# NTCSHTshield.net
KiCad netlist of a schematic drawn in EAGLE
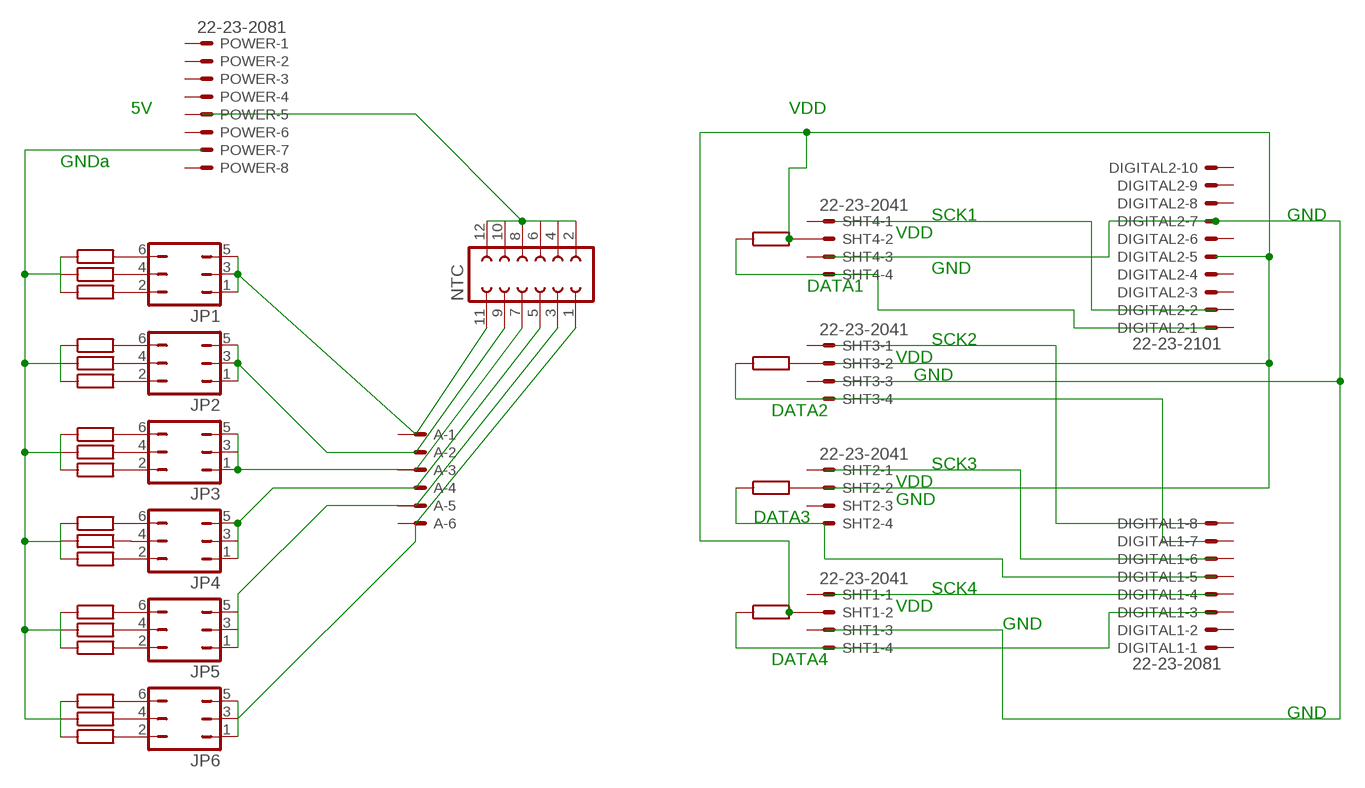
[diagram p0: schematic, sheet 1]

(export (version "E")
  (design (tool "Eeschema 10.0.6"))
  (components
    (comp (ref "A")
      (value "22-23-2061")
      (footprint "eagle-import:22-23-2061")
      (fields (field (name "MF") "MOLEX"))
      (libsource (lib "eagle-import") (part "22-23-2061"))
    )
    (comp (ref "DIGITAL1")
      (value "22-23-2081")
      (footprint "eagle-import:22-23-2081")
      (fields (field (name "MF") "MOLEX"))
      (libsource (lib "eagle-import") (part "22-23-2081"))
    )
    (comp (ref "DIGITAL2")
      (value "22-23-2101")
      (footprint "eagle-import:22-23-2101")
      (fields (field (name "MF") "MOLEX"))
      (libsource (lib "eagle-import") (part "22-23-2101"))
    )
    (comp (ref "JP1")
      (value "JP3Q")
      (footprint "eagle-import:JP3Q")
      (libsource (lib "eagle-import") (part "JP3Q"))
    )
    (comp (ref "JP2")
      (value "JP3Q")
      (footprint "eagle-import:JP3Q")
      (libsource (lib "eagle-import") (part "JP3Q"))
    )
    (comp (ref "JP3")
      (value "JP3Q")
      (footprint "eagle-import:JP3Q")
      (libsource (lib "eagle-import") (part "JP3Q"))
    )
    (comp (ref "JP4")
      (value "JP3Q")
      (footprint "eagle-import:JP3Q")
      (libsource (lib "eagle-import") (part "JP3Q"))
    )
    (comp (ref "JP5")
      (value "JP3Q")
      (footprint "eagle-import:JP3Q")
      (libsource (lib "eagle-import") (part "JP3Q"))
    )
    (comp (ref "JP6")
      (value "JP3Q")
      (footprint "eagle-import:JP3Q")
      (libsource (lib "eagle-import") (part "JP3Q"))
    )
    (comp (ref "NTC")
      (value "FE06-2")
      (footprint "eagle-import:FE06-2")
      (libsource (lib "eagle-import") (part "FE06-2"))
    )
    (comp (ref "POWER")
      (value "22-23-2081")
      (footprint "eagle-import:22-23-2081")
      (fields (field (name "MF") "MOLEX"))
      (libsource (lib "eagle-import") (part "22-23-2081"))
    )
    (comp (ref "SHT1")
      (value "22-23-2041")
      (footprint "eagle-import:22-23-2041")
      (fields (field (name "MF") "MOLEX"))
      (libsource (lib "eagle-import") (part "22-23-2041"))
    )
    (comp (ref "SHT2")
      (value "22-23-2041")
      (footprint "eagle-import:22-23-2041")
      (fields (field (name "MF") "MOLEX"))
      (libsource (lib "eagle-import") (part "22-23-2041"))
    )
    (comp (ref "SHT3")
      (value "22-23-2041")
      (footprint "eagle-import:22-23-2041")
      (fields (field (name "MF") "MOLEX"))
      (libsource (lib "eagle-import") (part "22-23-2041"))
    )
    (comp (ref "SHT4")
      (value "22-23-2041")
      (footprint "eagle-import:22-23-2041")
      (fields (field (name "MF") "MOLEX"))
      (libsource (lib "eagle-import") (part "22-23-2041"))
    )
  )
  (nets
    (net (code "1") (name "Net-(JP1-Pad1)") (class "Default")
      (node (ref "JP1") (pin "1") (pinfunction "1_1") (pintype "passive"))
      (node (ref "JP1") (pin "3") (pinfunction "3_3") (pintype "passive"))
      (node (ref "JP1") (pin "5") (pinfunction "5_5") (pintype "passive"))
      (node (ref "NTC") (pin "11") (pinfunction "11_11") (pintype "passive"))
    )
    (net (code "2") (name "Net-(JP2-Pad1)") (class "Default")
      (node (ref "JP2") (pin "1") (pinfunction "1_1") (pintype "passive"))
      (node (ref "JP2") (pin "3") (pinfunction "3_3") (pintype "passive"))
      (node (ref "JP2") (pin "5") (pinfunction "5_5") (pintype "passive"))
      (node (ref "NTC") (pin "9") (pinfunction "9_9") (pintype "passive"))
    )
    (net (code "3") (name "Net-(JP3-Pad1)") (class "Default")
      (node (ref "JP3") (pin "1") (pinfunction "1_1") (pintype "passive"))
      (node (ref "JP3") (pin "3") (pinfunction "3_3") (pintype "passive"))
      (node (ref "JP3") (pin "5") (pinfunction "5_5") (pintype "passive"))
      (node (ref "NTC") (pin "7") (pinfunction "7_7") (pintype "passive"))
    )
    (net (code "4") (name "Net-(JP4-Pad1)") (class "Default")
      (node (ref "JP4") (pin "1") (pinfunction "1_1") (pintype "passive"))
      (node (ref "JP4") (pin "3") (pinfunction "3_3") (pintype "passive"))
      (node (ref "JP4") (pin "5") (pinfunction "5_5") (pintype "passive"))
      (node (ref "NTC") (pin "5") (pinfunction "5_5") (pintype "passive"))
    )
    (net (code "5") (name "Net-(JP5-Pad1)") (class "Default")
      (node (ref "JP5") (pin "1") (pinfunction "1_1") (pintype "passive"))
      (node (ref "JP5") (pin "3") (pinfunction "3_3") (pintype "passive"))
      (node (ref "JP5") (pin "5") (pinfunction "5_5") (pintype "passive"))
      (node (ref "NTC") (pin "3") (pinfunction "3_3") (pintype "passive"))
    )
    (net (code "6") (name "Net-(JP6-Pad1)") (class "Default")
      (node (ref "JP6") (pin "1") (pinfunction "1_1") (pintype "passive"))
      (node (ref "JP6") (pin "3") (pinfunction "3_3") (pintype "passive"))
      (node (ref "JP6") (pin "5") (pinfunction "5_5") (pintype "passive"))
      (node (ref "NTC") (pin "1") (pinfunction "1_1") (pintype "passive"))
    )
    (net (code "7") (name "Net-(NTC-Pad10)") (class "Default")
      (node (ref "NTC") (pin "10") (pinfunction "10_10") (pintype "passive"))
      (node (ref "NTC") (pin "12") (pinfunction "12_12") (pintype "passive"))
      (node (ref "NTC") (pin "2") (pinfunction "2_2") (pintype "passive"))
      (node (ref "NTC") (pin "4") (pinfunction "4_4") (pintype "passive"))
      (node (ref "NTC") (pin "6") (pinfunction "6_6") (pintype "passive"))
      (node (ref "NTC") (pin "8") (pinfunction "8_8") (pintype "passive"))
    )
    (net (code "8") (name "unconnected-(AA-S-Pad1)") (class "Default")
      (node (ref "A") (pin "1") (pinfunction "S_1") (pintype "passive"))
    )
    (net (code "9") (name "unconnected-(AB-S-Pad2)") (class "Default")
      (node (ref "A") (pin "2") (pinfunction "S_2") (pintype "passive"))
    )
    (net (code "10") (name "unconnected-(AC-S-Pad3)") (class "Default")
      (node (ref "A") (pin "3") (pinfunction "S_3") (pintype "passive"))
    )
    (net (code "11") (name "unconnected-(AD-S-Pad4)") (class "Default")
      (node (ref "A") (pin "4") (pinfunction "S_4") (pintype "passive"))
    )
    (net (code "12") (name "unconnected-(AE-S-Pad5)") (class "Default")
      (node (ref "A") (pin "5") (pinfunction "S_5") (pintype "passive"))
    )
    (net (code "13") (name "unconnected-(AF-S-Pad6)") (class "Default")
      (node (ref "A") (pin "6") (pinfunction "S_6") (pintype "passive"))
    )
    (net (code "14") (name "unconnected-(DIGITAL1A-S-Pad1)") (class "Default")
      (node (ref "DIGITAL1") (pin "1") (pinfunction "S_1") (pintype "passive"))
    )
    (net (code "15") (name "unconnected-(DIGITAL1B-S-Pad2)") (class "Default")
      (node (ref "DIGITAL1") (pin "2") (pinfunction "S_2") (pintype "passive"))
    )
    (net (code "16") (name "unconnected-(DIGITAL1C-S-Pad3)") (class "Default")
      (node (ref "DIGITAL1") (pin "3") (pinfunction "S_3") (pintype "passive"))
    )
    (net (code "17") (name "unconnected-(DIGITAL1D-S-Pad4)") (class "Default")
      (node (ref "DIGITAL1") (pin "4") (pinfunction "S_4") (pintype "passive"))
    )
    (net (code "18") (name "unconnected-(DIGITAL1E-S-Pad5)") (class "Default")
      (node (ref "DIGITAL1") (pin "5") (pinfunction "S_5") (pintype "passive"))
    )
    (net (code "19") (name "unconnected-(DIGITAL1F-S-Pad6)") (class "Default")
      (node (ref "DIGITAL1") (pin "6") (pinfunction "S_6") (pintype "passive"))
    )
    (net (code "20") (name "unconnected-(DIGITAL1G-S-Pad7)") (class "Default")
      (node (ref "DIGITAL1") (pin "7") (pinfunction "S_7") (pintype "passive"))
    )
    (net (code "21") (name "unconnected-(DIGITAL1H-S-Pad8)") (class "Default")
      (node (ref "DIGITAL1") (pin "8") (pinfunction "S_8") (pintype "passive"))
    )
    (net (code "22") (name "unconnected-(DIGITAL2A-S-Pad1)") (class "Default")
      (node (ref "DIGITAL2") (pin "1") (pinfunction "S_1") (pintype "passive"))
    )
    (net (code "23") (name "unconnected-(DIGITAL2B-S-Pad10)") (class "Default")
      (node (ref "DIGITAL2") (pin "10") (pinfunction "S_10") (pintype "passive"))
    )
    (net (code "24") (name "unconnected-(DIGITAL2C-S-Pad2)") (class "Default")
      (node (ref "DIGITAL2") (pin "2") (pinfunction "S_2") (pintype "passive"))
    )
    (net (code "25") (name "unconnected-(DIGITAL2D-S-Pad3)") (class "Default")
      (node (ref "DIGITAL2") (pin "3") (pinfunction "S_3") (pintype "passive"))
    )
    (net (code "26") (name "unconnected-(DIGITAL2E-S-Pad4)") (class "Default")
      (node (ref "DIGITAL2") (pin "4") (pinfunction "S_4") (pintype "passive"))
    )
    (net (code "27") (name "unconnected-(DIGITAL2F-S-Pad5)") (class "Default")
      (node (ref "DIGITAL2") (pin "5") (pinfunction "S_5") (pintype "passive"))
    )
    (net (code "28") (name "unconnected-(DIGITAL2G-S-Pad6)") (class "Default")
      (node (ref "DIGITAL2") (pin "6") (pinfunction "S_6") (pintype "passive"))
    )
    (net (code "29") (name "unconnected-(DIGITAL2H-S-Pad7)") (class "Default")
      (node (ref "DIGITAL2") (pin "7") (pinfunction "S_7") (pintype "passive"))
    )
    (net (code "30") (name "unconnected-(DIGITAL2I-S-Pad8)") (class "Default")
      (node (ref "DIGITAL2") (pin "8") (pinfunction "S_8") (pintype "passive"))
    )
    (net (code "31") (name "unconnected-(DIGITAL2J-S-Pad9)") (class "Default")
      (node (ref "DIGITAL2") (pin "9") (pinfunction "S_9") (pintype "passive"))
    )
    (net (code "32") (name "unconnected-(JP1-Pad2)") (class "Default")
      (node (ref "JP1") (pin "2") (pinfunction "2_2") (pintype "passive"))
    )
    (net (code "33") (name "unconnected-(JP1-Pad4)") (class "Default")
      (node (ref "JP1") (pin "4") (pinfunction "4_4") (pintype "passive"))
    )
    (net (code "34") (name "unconnected-(JP1-Pad6)") (class "Default")
      (node (ref "JP1") (pin "6") (pinfunction "6_6") (pintype "passive"))
    )
    (net (code "35") (name "unconnected-(JP2-Pad2)") (class "Default")
      (node (ref "JP2") (pin "2") (pinfunction "2_2") (pintype "passive"))
    )
    (net (code "36") (name "unconnected-(JP2-Pad4)") (class "Default")
      (node (ref "JP2") (pin "4") (pinfunction "4_4") (pintype "passive"))
    )
    (net (code "37") (name "unconnected-(JP2-Pad6)") (class "Default")
      (node (ref "JP2") (pin "6") (pinfunction "6_6") (pintype "passive"))
    )
    (net (code "38") (name "unconnected-(JP3-Pad2)") (class "Default")
      (node (ref "JP3") (pin "2") (pinfunction "2_2") (pintype "passive"))
    )
    (net (code "39") (name "unconnected-(JP3-Pad4)") (class "Default")
      (node (ref "JP3") (pin "4") (pinfunction "4_4") (pintype "passive"))
    )
    (net (code "40") (name "unconnected-(JP3-Pad6)") (class "Default")
      (node (ref "JP3") (pin "6") (pinfunction "6_6") (pintype "passive"))
    )
    (net (code "41") (name "unconnected-(JP4-Pad2)") (class "Default")
      (node (ref "JP4") (pin "2") (pinfunction "2_2") (pintype "passive"))
    )
    (net (code "42") (name "unconnected-(JP4-Pad4)") (class "Default")
      (node (ref "JP4") (pin "4") (pinfunction "4_4") (pintype "passive"))
    )
    (net (code "43") (name "unconnected-(JP4-Pad6)") (class "Default")
      (node (ref "JP4") (pin "6") (pinfunction "6_6") (pintype "passive"))
    )
    (net (code "44") (name "unconnected-(JP5-Pad2)") (class "Default")
      (node (ref "JP5") (pin "2") (pinfunction "2_2") (pintype "passive"))
    )
    (net (code "45") (name "unconnected-(JP5-Pad4)") (class "Default")
      (node (ref "JP5") (pin "4") (pinfunction "4_4") (pintype "passive"))
    )
    (net (code "46") (name "unconnected-(JP5-Pad6)") (class "Default")
      (node (ref "JP5") (pin "6") (pinfunction "6_6") (pintype "passive"))
    )
    (net (code "47") (name "unconnected-(JP6-Pad2)") (class "Default")
      (node (ref "JP6") (pin "2") (pinfunction "2_2") (pintype "passive"))
    )
    (net (code "48") (name "unconnected-(JP6-Pad4)") (class "Default")
      (node (ref "JP6") (pin "4") (pinfunction "4_4") (pintype "passive"))
    )
    (net (code "49") (name "unconnected-(JP6-Pad6)") (class "Default")
      (node (ref "JP6") (pin "6") (pinfunction "6_6") (pintype "passive"))
    )
    (net (code "50") (name "unconnected-(POWERA-S-Pad1)") (class "Default")
      (node (ref "POWER") (pin "1") (pinfunction "S_1") (pintype "passive"))
    )
    (net (code "51") (name "unconnected-(POWERB-S-Pad2)") (class "Default")
      (node (ref "POWER") (pin "2") (pinfunction "S_2") (pintype "passive"))
    )
    (net (code "52") (name "unconnected-(POWERC-S-Pad3)") (class "Default")
      (node (ref "POWER") (pin "3") (pinfunction "S_3") (pintype "passive"))
    )
    (net (code "53") (name "unconnected-(POWERD-S-Pad4)") (class "Default")
      (node (ref "POWER") (pin "4") (pinfunction "S_4") (pintype "passive"))
    )
    (net (code "54") (name "unconnected-(POWERE-S-Pad5)") (class "Default")
      (node (ref "POWER") (pin "5") (pinfunction "S_5") (pintype "passive"))
    )
    (net (code "55") (name "unconnected-(POWERF-S-Pad6)") (class "Default")
      (node (ref "POWER") (pin "6") (pinfunction "S_6") (pintype "passive"))
    )
    (net (code "56") (name "unconnected-(POWERG-S-Pad7)") (class "Default")
      (node (ref "POWER") (pin "7") (pinfunction "S_7") (pintype "passive"))
    )
    (net (code "57") (name "unconnected-(POWERH-S-Pad8)") (class "Default")
      (node (ref "POWER") (pin "8") (pinfunction "S_8") (pintype "passive"))
    )
    (net (code "58") (name "unconnected-(SHT1A-S-Pad1)") (class "Default")
      (node (ref "SHT1") (pin "1") (pinfunction "S_1") (pintype "passive"))
    )
    (net (code "59") (name "unconnected-(SHT1B-S-Pad2)") (class "Default")
      (node (ref "SHT1") (pin "2") (pinfunction "S_2") (pintype "passive"))
    )
    (net (code "60") (name "unconnected-(SHT1C-S-Pad3)") (class "Default")
      (node (ref "SHT1") (pin "3") (pinfunction "S_3") (pintype "passive"))
    )
    (net (code "61") (name "unconnected-(SHT1D-S-Pad4)") (class "Default")
      (node (ref "SHT1") (pin "4") (pinfunction "S_4") (pintype "passive"))
    )
    (net (code "62") (name "unconnected-(SHT2A-S-Pad1)") (class "Default")
      (node (ref "SHT2") (pin "1") (pinfunction "S_1") (pintype "passive"))
    )
    (net (code "63") (name "unconnected-(SHT2B-S-Pad2)") (class "Default")
      (node (ref "SHT2") (pin "2") (pinfunction "S_2") (pintype "passive"))
    )
    (net (code "64") (name "unconnected-(SHT2C-S-Pad3)") (class "Default")
      (node (ref "SHT2") (pin "3") (pinfunction "S_3") (pintype "passive"))
    )
    (net (code "65") (name "unconnected-(SHT2D-S-Pad4)") (class "Default")
      (node (ref "SHT2") (pin "4") (pinfunction "S_4") (pintype "passive"))
    )
    (net (code "66") (name "unconnected-(SHT3A-S-Pad1)") (class "Default")
      (node (ref "SHT3") (pin "1") (pinfunction "S_1") (pintype "passive"))
    )
    (net (code "67") (name "unconnected-(SHT3B-S-Pad2)") (class "Default")
      (node (ref "SHT3") (pin "2") (pinfunction "S_2") (pintype "passive"))
    )
    (net (code "68") (name "unconnected-(SHT3C-S-Pad3)") (class "Default")
      (node (ref "SHT3") (pin "3") (pinfunction "S_3") (pintype "passive"))
    )
    (net (code "69") (name "unconnected-(SHT3D-S-Pad4)") (class "Default")
      (node (ref "SHT3") (pin "4") (pinfunction "S_4") (pintype "passive"))
    )
    (net (code "70") (name "unconnected-(SHT4A-S-Pad1)") (class "Default")
      (node (ref "SHT4") (pin "1") (pinfunction "S_1") (pintype "passive"))
    )
    (net (code "71") (name "unconnected-(SHT4B-S-Pad2)") (class "Default")
      (node (ref "SHT4") (pin "2") (pinfunction "S_2") (pintype "passive"))
    )
    (net (code "72") (name "unconnected-(SHT4C-S-Pad3)") (class "Default")
      (node (ref "SHT4") (pin "3") (pinfunction "S_3") (pintype "passive"))
    )
    (net (code "73") (name "unconnected-(SHT4D-S-Pad4)") (class "Default")
      (node (ref "SHT4") (pin "4") (pinfunction "S_4") (pintype "passive"))
    )
  )
)
